# infinity_mirror_rev_g.net
KiCad netlist of a schematic drawn in EAGLE
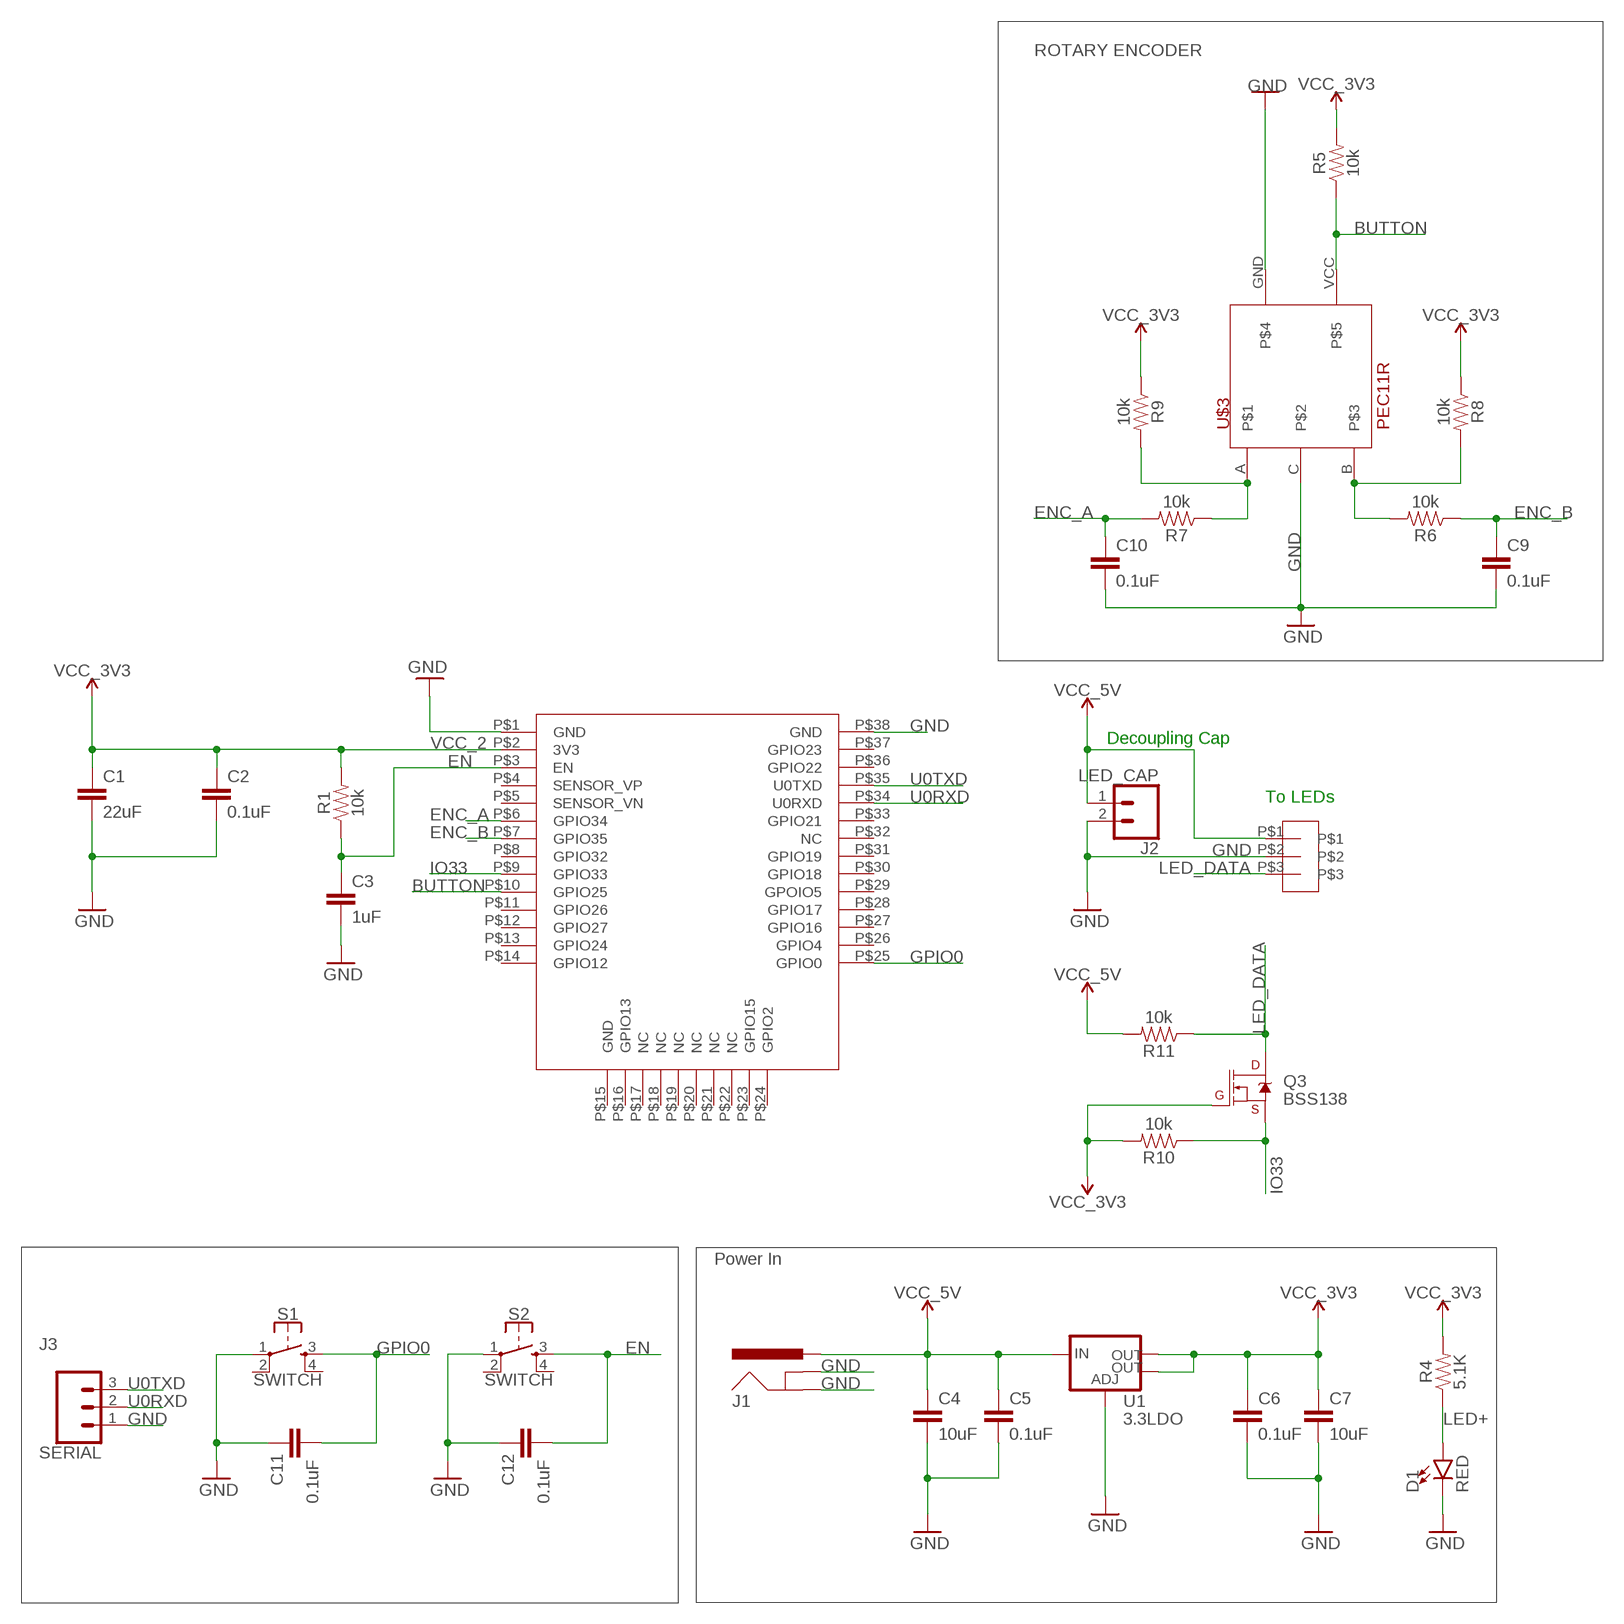
[diagram p0: schematic, sheet 1]

(export (version "E")
  (design (tool "Eeschema 10.0.6"))
  (components
    (comp (ref "C1")
      (value "22uF")
      (footprint "eagle-import:0805")
      (libsource (lib "eagle-import") (part "CAPACITOR"))
    )
    (comp (ref "C2")
      (value "0.1uF")
      (footprint "eagle-import:0805")
      (libsource (lib "eagle-import") (part "CAPACITOR"))
    )
    (comp (ref "C3")
      (value "1uF")
      (footprint "eagle-import:0805")
      (libsource (lib "eagle-import") (part "CAPACITOR"))
    )
    (comp (ref "C4")
      (value "10uF")
      (footprint "eagle-import:0805")
      (libsource (lib "eagle-import") (part "CAPACITOR"))
    )
    (comp (ref "C5")
      (value "0.1uF")
      (footprint "eagle-import:0805")
      (libsource (lib "eagle-import") (part "CAPACITOR"))
    )
    (comp (ref "C6")
      (value "0.1uF")
      (footprint "eagle-import:0805")
      (libsource (lib "eagle-import") (part "CAPACITOR"))
    )
    (comp (ref "C7")
      (value "10uF")
      (footprint "eagle-import:0805")
      (libsource (lib "eagle-import") (part "CAPACITOR"))
    )
    (comp (ref "C9")
      (value "0.1uF")
      (footprint "eagle-import:0805")
      (libsource (lib "eagle-import") (part "CAPACITOR"))
    )
    (comp (ref "C10")
      (value "0.1uF")
      (footprint "eagle-import:0805")
      (libsource (lib "eagle-import") (part "CAPACITOR"))
    )
    (comp (ref "C11")
      (value "0.1uF")
      (footprint "eagle-import:0805")
      (libsource (lib "eagle-import") (part "CAPACITOR"))
    )
    (comp (ref "C12")
      (value "0.1uF")
      (footprint "eagle-import:0805")
      (libsource (lib "eagle-import") (part "CAPACITOR"))
    )
    (comp (ref "D1")
      (value "RED")
      (footprint "eagle-import:LED-1206")
      (libsource (lib "eagle-import") (part "LED-RED1206"))
    )
    (comp (ref "J1")
      (value "POWER_JACKPTH_BREAD")
      (footprint "eagle-import:POWER_JACK_PTH_BREAD")
      (libsource (lib "eagle-import") (part "POWER_JACKPTH_BREAD"))
    )
    (comp (ref "J2")
      (value "LED_CAP")
      (footprint "eagle-import:1X02")
      (libsource (lib "eagle-import") (part "CONN_02"))
    )
    (comp (ref "J3")
      (value "SERIAL")
      (footprint "eagle-import:1X03")
      (libsource (lib "eagle-import") (part "CONN_03"))
    )
    (comp (ref "Q3")
      (value "BSS138")
      (footprint "eagle-import:SOT23-3")
      (libsource (lib "eagle-import") (part "MOSFET-NCH-BSS138"))
    )
    (comp (ref "R1")
      (value "10k")
      (footprint "eagle-import:0805")
      (libsource (lib "eagle-import") (part "RESISTOR"))
    )
    (comp (ref "R4")
      (value "5.1K")
      (footprint "eagle-import:0805")
      (libsource (lib "eagle-import") (part "RESISTOR"))
    )
    (comp (ref "R5")
      (value "10k")
      (footprint "eagle-import:0805")
      (libsource (lib "eagle-import") (part "RESISTOR"))
    )
    (comp (ref "R6")
      (value "10k")
      (footprint "eagle-import:0805")
      (libsource (lib "eagle-import") (part "RESISTOR"))
    )
    (comp (ref "R7")
      (value "10k")
      (footprint "eagle-import:0805")
      (libsource (lib "eagle-import") (part "RESISTOR"))
    )
    (comp (ref "R8")
      (value "10k")
      (footprint "eagle-import:0805")
      (libsource (lib "eagle-import") (part "RESISTOR"))
    )
    (comp (ref "R9")
      (value "10k")
      (footprint "eagle-import:0805")
      (libsource (lib "eagle-import") (part "RESISTOR"))
    )
    (comp (ref "R10")
      (value "10k")
      (footprint "eagle-import:0805")
      (libsource (lib "eagle-import") (part "RESISTOR"))
    )
    (comp (ref "R11")
      (value "10k")
      (footprint "eagle-import:0805")
      (libsource (lib "eagle-import") (part "RESISTOR"))
    )
    (comp (ref "S1")
      (value "SWITCH")
      (footprint "eagle-import:TACTILE_SWITCH_SMD_5.2MM")
      (libsource (lib "eagle-import") (part "MOMENTARY-SWITCH-SPST-2-SMD-5.2MM-TALL"))
    )
    (comp (ref "S2")
      (value "SWITCH")
      (footprint "eagle-import:TACTILE_SWITCH_SMD_5.2MM")
      (libsource (lib "eagle-import") (part "MOMENTARY-SWITCH-SPST-2-SMD-5.2MM-TALL"))
    )
    (comp (ref "U$1")
      (value "ESP32-WROOM-32E")
      (footprint "eagle-import:ESP32-WROOM-32E")
      (libsource (lib "eagle-import") (part "ESP32-WROOM-32E"))
    )
    (comp (ref "U$2")
      (value "3-PIN-JST")
      (footprint "eagle-import:3-PIN-JST")
      (libsource (lib "eagle-import") (part "3-PIN-JST"))
    )
    (comp (ref "U$3")
      (value "PEC11R")
      (footprint "eagle-import:PEC11R-4320F-S0012")
      (libsource (lib "eagle-import") (part "PEC11R_ROTARY_ENCODER"))
    )
    (comp (ref "U1")
      (value "3.3LDO")
      (footprint "eagle-import:SOT223")
      (libsource (lib "eagle-import") (part "V_REG_LM1117SOT223"))
    )
  )
  (nets
    (net (code "1") (name "/BUTTON") (class "Default")
      (node (ref "R5") (pin "1") (pinfunction "1_1") (pintype "passive"))
      (node (ref "U$1") (pin "P$10") (pinfunction "GPIO25_P$10") (pintype "bidirectional"))
      (node (ref "U$3") (pin "VCC") (pinfunction "P$5_VCC") (pintype "bidirectional"))
    )
    (net (code "2") (name "/EN") (class "Default")
      (node (ref "C12") (pin "2") (pinfunction "2_2") (pintype "passive"))
      (node (ref "C3") (pin "1") (pinfunction "1_1") (pintype "passive"))
      (node (ref "R1") (pin "1") (pinfunction "1_1") (pintype "passive"))
      (node (ref "S2") (pin "3") (pinfunction "3_3") (pintype "passive"))
      (node (ref "U$1") (pin "P$3") (pinfunction "EN_P$3") (pintype "bidirectional"))
    )
    (net (code "3") (name "/ENC_A") (class "Default")
      (node (ref "C10") (pin "1") (pinfunction "1_1") (pintype "passive"))
      (node (ref "R7") (pin "2") (pinfunction "2_2") (pintype "passive"))
      (node (ref "U$1") (pin "P$6") (pinfunction "GPIO34_P$6") (pintype "bidirectional"))
    )
    (net (code "4") (name "/ENC_B") (class "Default")
      (node (ref "C9") (pin "1") (pinfunction "1_1") (pintype "passive"))
      (node (ref "R6") (pin "1") (pinfunction "1_1") (pintype "passive"))
      (node (ref "U$1") (pin "P$7") (pinfunction "GPIO35_P$7") (pintype "bidirectional"))
    )
    (net (code "5") (name "/GPIO0") (class "Default")
      (node (ref "C11") (pin "2") (pinfunction "2_2") (pintype "passive"))
      (node (ref "S1") (pin "3") (pinfunction "3_3") (pintype "passive"))
      (node (ref "U$1") (pin "P$25") (pinfunction "GPIO0_P$25") (pintype "bidirectional"))
    )
    (net (code "6") (name "/IO33") (class "Default")
      (node (ref "Q3") (pin "2") (pinfunction "S_2") (pintype "bidirectional"))
      (node (ref "R10") (pin "1") (pinfunction "1_1") (pintype "passive"))
      (node (ref "U$1") (pin "P$9") (pinfunction "GPIO33_P$9") (pintype "bidirectional"))
    )
    (net (code "7") (name "/LED+") (class "Default")
      (node (ref "D1") (pin "A") (pinfunction "A_A") (pintype "passive"))
      (node (ref "R4") (pin "1") (pinfunction "1_1") (pintype "passive"))
    )
    (net (code "8") (name "/LED_DATA") (class "Default")
      (node (ref "Q3") (pin "3") (pinfunction "D_3") (pintype "bidirectional"))
      (node (ref "R11") (pin "1") (pinfunction "1_1") (pintype "passive"))
      (node (ref "U$2") (pin "P$3") (pinfunction "P$3_P$3") (pintype "bidirectional"))
    )
    (net (code "9") (name "/U0RXD") (class "Default")
      (node (ref "J3") (pin "2") (pinfunction "2_2") (pintype "passive"))
      (node (ref "U$1") (pin "P$34") (pinfunction "U0RXD_P$34") (pintype "bidirectional"))
    )
    (net (code "10") (name "/U0TXD") (class "Default")
      (node (ref "J3") (pin "3") (pinfunction "3_3") (pintype "passive"))
      (node (ref "U$1") (pin "P$35") (pinfunction "U0TXD_P$35") (pintype "bidirectional"))
    )
    (net (code "11") (name "GND") (class "Default")
      (node (ref "C1") (pin "2") (pinfunction "2_2") (pintype "passive"))
      (node (ref "C10") (pin "2") (pinfunction "2_2") (pintype "passive"))
      (node (ref "C11") (pin "1") (pinfunction "1_1") (pintype "passive"))
      (node (ref "C12") (pin "1") (pinfunction "1_1") (pintype "passive"))
      (node (ref "C2") (pin "2") (pinfunction "2_2") (pintype "passive"))
      (node (ref "C3") (pin "2") (pinfunction "2_2") (pintype "passive"))
      (node (ref "C4") (pin "2") (pinfunction "2_2") (pintype "passive"))
      (node (ref "C5") (pin "2") (pinfunction "2_2") (pintype "passive"))
      (node (ref "C6") (pin "2") (pinfunction "2_2") (pintype "passive"))
      (node (ref "C7") (pin "2") (pinfunction "2_2") (pintype "passive"))
      (node (ref "C9") (pin "2") (pinfunction "2_2") (pintype "passive"))
      (node (ref "D1") (pin "C") (pinfunction "C_C") (pintype "passive"))
      (node (ref "J1") (pin "GND") (pinfunction "GND_GND") (pintype "bidirectional"))
      (node (ref "J1") (pin "GNDBREAK") (pinfunction "GNDBREAK_GNDBREAK") (pintype "bidirectional"))
      (node (ref "J2") (pin "2") (pinfunction "2_2") (pintype "passive"))
      (node (ref "J3") (pin "1") (pinfunction "1_1") (pintype "passive"))
      (node (ref "S1") (pin "1") (pinfunction "1_1") (pintype "passive"))
      (node (ref "S2") (pin "1") (pinfunction "1_1") (pintype "passive"))
      (node (ref "U$1") (pin "P$1") (pinfunction "GND_P$1") (pintype "bidirectional"))
      (node (ref "U$1") (pin "P$38") (pinfunction "GND_P$38") (pintype "bidirectional"))
      (node (ref "U$2") (pin "P$2") (pinfunction "P$2_P$2") (pintype "bidirectional"))
      (node (ref "U$3") (pin "C") (pinfunction "P$2_C") (pintype "bidirectional"))
      (node (ref "U$3") (pin "GND") (pinfunction "P$4_GND") (pintype "bidirectional"))
      (node (ref "U1") (pin "1") (pinfunction "ADJ_1") (pintype "input"))
    )
    (net (code "12") (name "Net-(U$3-P$1)") (class "Default")
      (node (ref "R7") (pin "1") (pinfunction "1_1") (pintype "passive"))
      (node (ref "R9") (pin "2") (pinfunction "2_2") (pintype "passive"))
      (node (ref "U$3") (pin "A") (pinfunction "P$1_A") (pintype "bidirectional"))
    )
    (net (code "13") (name "Net-(U$3-P$3)") (class "Default")
      (node (ref "R6") (pin "2") (pinfunction "2_2") (pintype "passive"))
      (node (ref "R8") (pin "2") (pinfunction "2_2") (pintype "passive"))
      (node (ref "U$3") (pin "B") (pinfunction "P$3_B") (pintype "bidirectional"))
    )
    (net (code "14") (name "VCC_3V3") (class "Default")
      (node (ref "C1") (pin "1") (pinfunction "1_1") (pintype "passive"))
      (node (ref "C2") (pin "1") (pinfunction "1_1") (pintype "passive"))
      (node (ref "C6") (pin "1") (pinfunction "1_1") (pintype "passive"))
      (node (ref "C7") (pin "1") (pinfunction "1_1") (pintype "passive"))
      (node (ref "Q3") (pin "1") (pinfunction "G_1") (pintype "bidirectional"))
      (node (ref "R1") (pin "2") (pinfunction "2_2") (pintype "passive"))
      (node (ref "R10") (pin "2") (pinfunction "2_2") (pintype "passive"))
      (node (ref "R4") (pin "2") (pinfunction "2_2") (pintype "passive"))
      (node (ref "R5") (pin "2") (pinfunction "2_2") (pintype "passive"))
      (node (ref "R8") (pin "1") (pinfunction "1_1") (pintype "passive"))
      (node (ref "R9") (pin "1") (pinfunction "1_1") (pintype "passive"))
      (node (ref "U$1") (pin "P$2") (pinfunction "3V3_P$2") (pintype "bidirectional"))
      (node (ref "U1") (pin "2") (pinfunction "OUT_2") (pintype "output"))
      (node (ref "U1") (pin "4") (pinfunction "OUT_4") (pintype "output"))
    )
    (net (code "15") (name "VCC_5V") (class "Default")
      (node (ref "C4") (pin "1") (pinfunction "1_1") (pintype "passive"))
      (node (ref "C5") (pin "1") (pinfunction "1_1") (pintype "passive"))
      (node (ref "J1") (pin "PWR") (pinfunction "PWR_PWR") (pintype "bidirectional"))
      (node (ref "J2") (pin "1") (pinfunction "1_1") (pintype "passive"))
      (node (ref "R11") (pin "2") (pinfunction "2_2") (pintype "passive"))
      (node (ref "U$2") (pin "P$1") (pinfunction "P$1_P$1") (pintype "bidirectional"))
      (node (ref "U1") (pin "3") (pinfunction "IN_3") (pintype "input"))
    )
    (net (code "16") (name "unconnected-(S1-Pad2)") (class "Default")
      (node (ref "S1") (pin "2") (pinfunction "2_2") (pintype "passive"))
    )
    (net (code "17") (name "unconnected-(S1-Pad4)") (class "Default")
      (node (ref "S1") (pin "4") (pinfunction "4_4") (pintype "passive"))
    )
    (net (code "18") (name "unconnected-(S2-Pad2)") (class "Default")
      (node (ref "S2") (pin "2") (pinfunction "2_2") (pintype "passive"))
    )
    (net (code "19") (name "unconnected-(S2-Pad4)") (class "Default")
      (node (ref "S2") (pin "4") (pinfunction "4_4") (pintype "passive"))
    )
    (net (code "20") (name "unconnected-(U$1-GND-PadP$15)") (class "Default")
      (node (ref "U$1") (pin "P$15") (pinfunction "GND_P$15") (pintype "bidirectional"))
    )
    (net (code "21") (name "unconnected-(U$1-GPIO2-PadP$24)") (class "Default")
      (node (ref "U$1") (pin "P$24") (pinfunction "GPIO2_P$24") (pintype "bidirectional"))
    )
    (net (code "22") (name "unconnected-(U$1-GPIO4-PadP$26)") (class "Default")
      (node (ref "U$1") (pin "P$26") (pinfunction "GPIO4_P$26") (pintype "bidirectional"))
    )
    (net (code "23") (name "unconnected-(U$1-GPIO12-PadP$14)") (class "Default")
      (node (ref "U$1") (pin "P$14") (pinfunction "GPIO12_P$14") (pintype "bidirectional"))
    )
    (net (code "24") (name "unconnected-(U$1-GPIO13-PadP$16)") (class "Default")
      (node (ref "U$1") (pin "P$16") (pinfunction "GPIO13_P$16") (pintype "bidirectional"))
    )
    (net (code "25") (name "unconnected-(U$1-GPIO15-PadP$23)") (class "Default")
      (node (ref "U$1") (pin "P$23") (pinfunction "GPIO15_P$23") (pintype "bidirectional"))
    )
    (net (code "26") (name "unconnected-(U$1-GPIO16-PadP$27)") (class "Default")
      (node (ref "U$1") (pin "P$27") (pinfunction "GPIO16_P$27") (pintype "bidirectional"))
    )
    (net (code "27") (name "unconnected-(U$1-GPIO17-PadP$28)") (class "Default")
      (node (ref "U$1") (pin "P$28") (pinfunction "GPIO17_P$28") (pintype "bidirectional"))
    )
    (net (code "28") (name "unconnected-(U$1-GPIO18-PadP$30)") (class "Default")
      (node (ref "U$1") (pin "P$30") (pinfunction "GPIO18_P$30") (pintype "bidirectional"))
    )
    (net (code "29") (name "unconnected-(U$1-GPIO19-PadP$31)") (class "Default")
      (node (ref "U$1") (pin "P$31") (pinfunction "GPIO19_P$31") (pintype "bidirectional"))
    )
    (net (code "30") (name "unconnected-(U$1-GPIO21-PadP$33)") (class "Default")
      (node (ref "U$1") (pin "P$33") (pinfunction "GPIO21_P$33") (pintype "bidirectional"))
    )
    (net (code "31") (name "unconnected-(U$1-GPIO22-PadP$36)") (class "Default")
      (node (ref "U$1") (pin "P$36") (pinfunction "GPIO22_P$36") (pintype "bidirectional"))
    )
    (net (code "32") (name "unconnected-(U$1-GPIO23-PadP$37)") (class "Default")
      (node (ref "U$1") (pin "P$37") (pinfunction "GPIO23_P$37") (pintype "bidirectional"))
    )
    (net (code "33") (name "unconnected-(U$1-GPIO24-PadP$13)") (class "Default")
      (node (ref "U$1") (pin "P$13") (pinfunction "GPIO24_P$13") (pintype "bidirectional"))
    )
    (net (code "34") (name "unconnected-(U$1-GPIO26-PadP$11)") (class "Default")
      (node (ref "U$1") (pin "P$11") (pinfunction "GPIO26_P$11") (pintype "bidirectional"))
    )
    (net (code "35") (name "unconnected-(U$1-GPIO27-PadP$12)") (class "Default")
      (node (ref "U$1") (pin "P$12") (pinfunction "GPIO27_P$12") (pintype "bidirectional"))
    )
    (net (code "36") (name "unconnected-(U$1-GPIO32-PadP$8)") (class "Default")
      (node (ref "U$1") (pin "P$8") (pinfunction "GPIO32_P$8") (pintype "bidirectional"))
    )
    (net (code "37") (name "unconnected-(U$1-GPOIO5-PadP$29)") (class "Default")
      (node (ref "U$1") (pin "P$29") (pinfunction "GPOIO5_P$29") (pintype "bidirectional"))
    )
    (net (code "38") (name "unconnected-(U$1-NC-PadP$17)") (class "Default")
      (node (ref "U$1") (pin "P$17") (pinfunction "NC_P$17") (pintype "bidirectional"))
    )
    (net (code "39") (name "unconnected-(U$1-NC-PadP$18)") (class "Default")
      (node (ref "U$1") (pin "P$18") (pinfunction "NC_P$18") (pintype "bidirectional"))
    )
    (net (code "40") (name "unconnected-(U$1-NC-PadP$19)") (class "Default")
      (node (ref "U$1") (pin "P$19") (pinfunction "NC_P$19") (pintype "bidirectional"))
    )
    (net (code "41") (name "unconnected-(U$1-NC-PadP$20)") (class "Default")
      (node (ref "U$1") (pin "P$20") (pinfunction "NC_P$20") (pintype "bidirectional"))
    )
    (net (code "42") (name "unconnected-(U$1-NC-PadP$21)") (class "Default")
      (node (ref "U$1") (pin "P$21") (pinfunction "NC_P$21") (pintype "bidirectional"))
    )
    (net (code "43") (name "unconnected-(U$1-NC-PadP$22)") (class "Default")
      (node (ref "U$1") (pin "P$22") (pinfunction "NC_P$22") (pintype "bidirectional"))
    )
    (net (code "44") (name "unconnected-(U$1-NC-PadP$32)") (class "Default")
      (node (ref "U$1") (pin "P$32") (pinfunction "NC_P$32") (pintype "bidirectional"))
    )
    (net (code "45") (name "unconnected-(U$1-SENSOR_VN-PadP$5)") (class "Default")
      (node (ref "U$1") (pin "P$5") (pinfunction "SENSOR_VN_P$5") (pintype "bidirectional"))
    )
    (net (code "46") (name "unconnected-(U$1-SENSOR_VP-PadP$4)") (class "Default")
      (node (ref "U$1") (pin "P$4") (pinfunction "SENSOR_VP_P$4") (pintype "bidirectional"))
    )
  )
)
